# acoms_bec.net
KiCad netlist of a schematic drawn in EAGLE
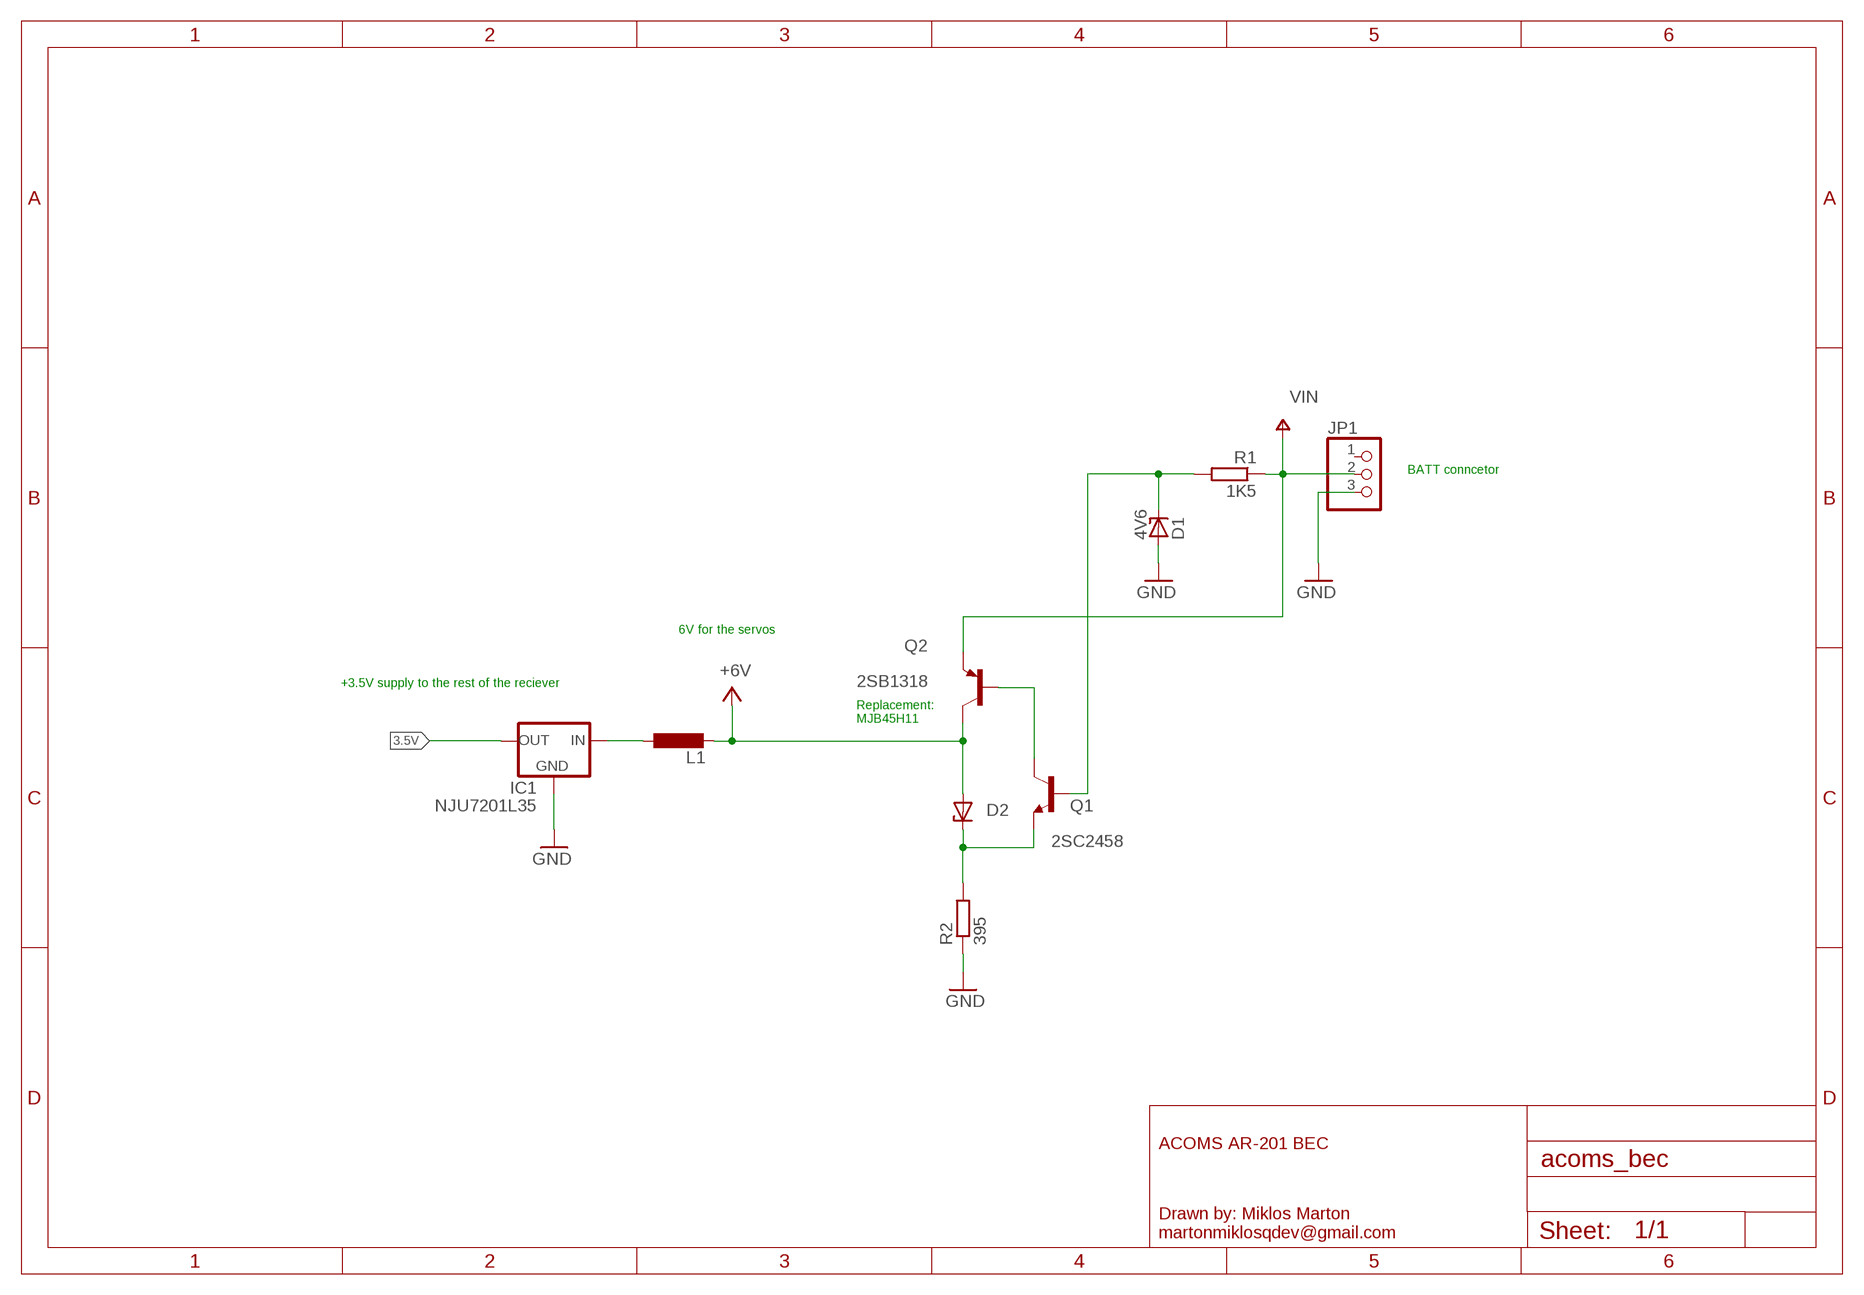
[diagram p0: schematic, sheet 1]

(export (version "E")
  (design (tool "Eeschema 10.0.6"))
  (components
    (comp (ref "D1")
      (value "4V6")
      (footprint "eagle-import:ZDIO-2.5")
      (libsource (lib "eagle-import") (part "ZENER-DIODEZD-2.5"))
    )
    (comp (ref "D2")
      (value "ZENER-DIODEZD-2.5")
      (footprint "eagle-import:ZDIO-2.5")
      (libsource (lib "eagle-import") (part "ZENER-DIODEZD-2.5"))
    )
    (comp (ref "IC1")
      (value "NJU7201L35")
      (footprint "eagle-import:TO-92")
      (libsource (lib "eagle-import") (part "V_REG_78XXTO-92"))
    )
    (comp (ref "JP1")
      (value "PINHD-1X3")
      (footprint "eagle-import:1X03")
      (libsource (lib "eagle-import") (part "PINHD-1X3"))
    )
    (comp (ref "L1")
      (value "L-EU0207/2V")
      (footprint "eagle-import:0207_2V")
      (libsource (lib "eagle-import") (part "L-EU0207/2V"))
    )
    (comp (ref "Q1")
      (value "2SC2458")
      (footprint "eagle-import:TO-92")
      (libsource (lib "eagle-import") (part "TRANSISTOR_BJT_NPN-TO-92-ECB"))
    )
    (comp (ref "Q2")
      (value "2SB1318")
      (footprint "eagle-import:TO-92")
      (libsource (lib "eagle-import") (part "TRANSISTOR_BJT_PNP-TO-92-ECB"))
    )
    (comp (ref "R1")
      (value "1K5")
      (footprint "eagle-import:0309V")
      (libsource (lib "eagle-import") (part "R-EU_0309/V"))
    )
    (comp (ref "R2")
      (value "395")
      (footprint "eagle-import:0309V")
      (libsource (lib "eagle-import") (part "R-EU_0309/V"))
    )
  )
  (nets
    (net (code "1") (name "+6V") (class "Default")
      (node (ref "D2") (pin "A") (pinfunction "A_A") (pintype "passive"))
      (node (ref "L1") (pin "2") (pinfunction "2_2") (pintype "passive"))
      (node (ref "Q2") (pin "2") (pinfunction "C_2") (pintype "passive"))
    )
    (net (code "2") (name "3.5V") (class "Default")
      (node (ref "IC1") (pin "3") (pinfunction "OUT_3") (pintype "output"))
    )
    (net (code "3") (name "GND") (class "Default")
      (node (ref "D1") (pin "A") (pinfunction "A_A") (pintype "passive"))
      (node (ref "IC1") (pin "1") (pinfunction "GND_1") (pintype "input"))
      (node (ref "JP1") (pin "3") (pinfunction "3_3") (pintype "passive"))
      (node (ref "R2") (pin "1") (pinfunction "1_1") (pintype "passive"))
    )
    (net (code "4") (name "Net-(IC1-IN)") (class "Default")
      (node (ref "IC1") (pin "2") (pinfunction "IN_2") (pintype "input"))
      (node (ref "L1") (pin "1") (pinfunction "1_1") (pintype "passive"))
    )
    (net (code "5") (name "Net-(Q1-B)") (class "Default")
      (node (ref "D1") (pin "C") (pinfunction "C_C") (pintype "passive"))
      (node (ref "Q1") (pin "3") (pinfunction "B_3") (pintype "passive"))
      (node (ref "R1") (pin "2") (pinfunction "2_2") (pintype "passive"))
    )
    (net (code "6") (name "Net-(Q1-C)") (class "Default")
      (node (ref "Q1") (pin "2") (pinfunction "C_2") (pintype "passive"))
      (node (ref "Q2") (pin "3") (pinfunction "B_3") (pintype "passive"))
    )
    (net (code "7") (name "Net-(Q1-E)") (class "Default")
      (node (ref "D2") (pin "C") (pinfunction "C_C") (pintype "passive"))
      (node (ref "Q1") (pin "1") (pinfunction "E_1") (pintype "passive"))
      (node (ref "R2") (pin "2") (pinfunction "2_2") (pintype "passive"))
    )
    (net (code "8") (name "VIN") (class "Default")
      (node (ref "JP1") (pin "2") (pinfunction "2_2") (pintype "passive"))
      (node (ref "Q2") (pin "1") (pinfunction "E_1") (pintype "passive"))
      (node (ref "R1") (pin "1") (pinfunction "1_1") (pintype "passive"))
    )
    (net (code "9") (name "unconnected-(JP1-Pad1)") (class "Default")
      (node (ref "JP1") (pin "1") (pinfunction "1_1") (pintype "passive"))
    )
  )
)
